# RoBeast_Power_Linear.net
KiCad netlist of a schematic drawn in Altium Designer
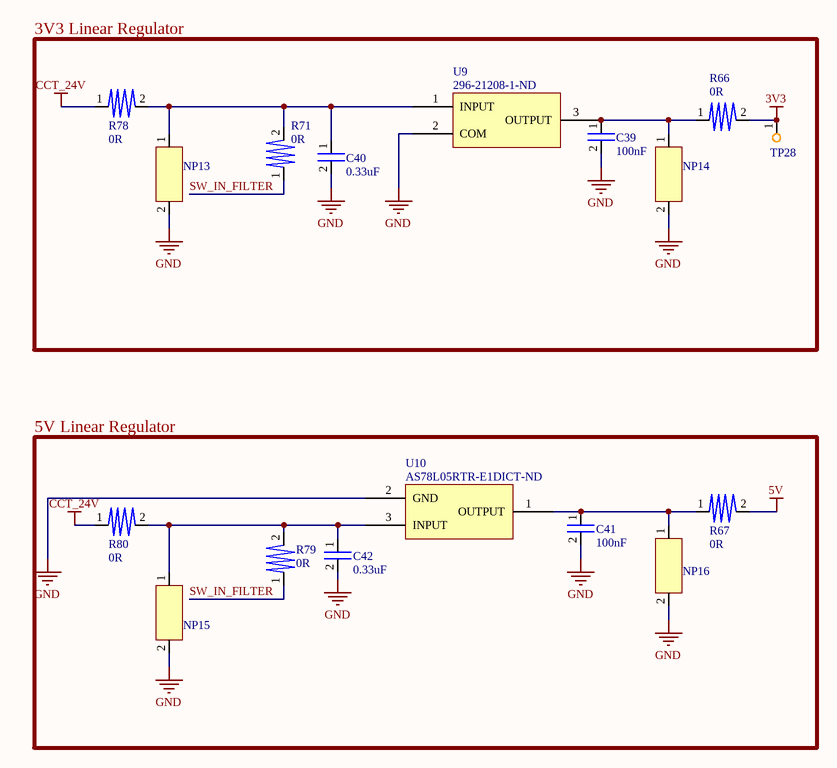
[diagram p0: RoBeast_Power_Linear.SchDoc]

(export (version "E")
  (design (tool "Eeschema 10.0.6"))
  (components
    (comp (ref "C39")
      (value "100nF")
      (footprint "0805")
      (fields
        (field (name "MANUFACTURER") "KEMET")
        (field (name "MANUFACTURER PART NUMBER") "C0805C104J5RACTU")
      )
      (libsource (lib "RoBeast_Schematic_Library") (part "C0805C104J5RAC7800"))
    )
    (comp (ref "C40")
      (value "0.33uF")
      (footprint "0805")
      (fields
        (field (name "MANUFACTURER") "KEMET")
        (field (name "MANUFACTURER PART NUMBER") "C0805C334K5RACTU")
      )
      (libsource (lib "RoBeast_Schematic_Library") (part "C0805C334K5RAC7800"))
    )
    (comp (ref "C41")
      (value "100nF")
      (footprint "0805")
      (fields
        (field (name "MANUFACTURER") "KEMET")
        (field (name "MANUFACTURER PART NUMBER") "C0805C104J5RACTU")
      )
      (libsource (lib "RoBeast_Schematic_Library") (part "C0805C104J5RAC7800"))
    )
    (comp (ref "C42")
      (value "0.33uF")
      (footprint "0805")
      (fields
        (field (name "MANUFACTURER") "KEMET")
        (field (name "MANUFACTURER PART NUMBER") "C0805C334K5RACTU")
      )
      (libsource (lib "RoBeast_Schematic_Library") (part "C0805C334K5RAC7800"))
    )
    (comp (ref "NP13")
      (value "Not Populated")
      (footprint "0805")
      (libsource (lib "RoBeast_Schematic_Library") (part "NP"))
    )
    (comp (ref "NP14")
      (value "Not Populated")
      (footprint "0805")
      (libsource (lib "RoBeast_Schematic_Library") (part "NP"))
    )
    (comp (ref "NP15")
      (value "Not Populated")
      (footprint "0805")
      (libsource (lib "RoBeast_Schematic_Library") (part "NP"))
    )
    (comp (ref "NP16")
      (value "Not Populated")
      (footprint "0805")
      (libsource (lib "RoBeast_Schematic_Library") (part "NP"))
    )
    (comp (ref "R66")
      (value "0R")
      (footprint "0805")
      (description "Fixed Resistor, Metal Glaze/thick Film, 0.125W, 0ohm, Surface Mount, 0805")
      (fields
        (field (name "MANUFACTURER") "Stackpole Electronics")
        (field (name "MANUFACTURER PART NUMBER") "RMCF0805ZT0R00")
      )
      (libsource (lib "RoBeast_Schematic_Library") (part "RMCF0805ZT0R00"))
    )
    (comp (ref "R67")
      (value "0R")
      (footprint "0805")
      (description "Fixed Resistor, Metal Glaze/thick Film, 0.125W, 0ohm, Surface Mount, 0805")
      (fields
        (field (name "MANUFACTURER") "Stackpole Electronics")
        (field (name "MANUFACTURER PART NUMBER") "RMCF0805ZT0R00")
      )
      (libsource (lib "RoBeast_Schematic_Library") (part "RMCF0805ZT0R00"))
    )
    (comp (ref "R71")
      (value "0R")
      (footprint "0805")
      (description "Fixed Resistor, Metal Glaze/thick Film, 0.125W, 0ohm, Surface Mount, 0805")
      (fields
        (field (name "MANUFACTURER") "Stackpole Electronics")
        (field (name "MANUFACTURER PART NUMBER") "RMCF0805ZT0R00")
      )
      (libsource (lib "RoBeast_Schematic_Library") (part "RMCF0805ZT0R00"))
    )
    (comp (ref "R78")
      (value "0R")
      (footprint "0805")
      (description "Fixed Resistor, Metal Glaze/thick Film, 0.125W, 0ohm, Surface Mount, 0805")
      (fields
        (field (name "MANUFACTURER") "Stackpole Electronics")
        (field (name "MANUFACTURER PART NUMBER") "RMCF0805ZT0R00")
      )
      (libsource (lib "RoBeast_Schematic_Library") (part "RMCF0805ZT0R00"))
    )
    (comp (ref "R79")
      (value "0R")
      (footprint "0805")
      (description "Fixed Resistor, Metal Glaze/thick Film, 0.125W, 0ohm, Surface Mount, 0805")
      (fields
        (field (name "MANUFACTURER") "Stackpole Electronics")
        (field (name "MANUFACTURER PART NUMBER") "RMCF0805ZT0R00")
      )
      (libsource (lib "RoBeast_Schematic_Library") (part "RMCF0805ZT0R00"))
    )
    (comp (ref "R80")
      (value "0R")
      (footprint "0805")
      (description "Fixed Resistor, Metal Glaze/thick Film, 0.125W, 0ohm, Surface Mount, 0805")
      (fields
        (field (name "MANUFACTURER") "Stackpole Electronics")
        (field (name "MANUFACTURER PART NUMBER") "RMCF0805ZT0R00")
      )
      (libsource (lib "RoBeast_Schematic_Library") (part "RMCF0805ZT0R00"))
    )
    (comp (ref "TP28")
      (value "Test Point")
      (footprint "Test Point")
      (libsource (lib "RoBeast_Schematic_Library") (part "Test Point"))
    )
    (comp (ref "U9")
      (value "Fixed 3V3 Voltage Regulator")
      (footprint "UA78M33CKVURG3")
      (description "Fixed Positive Standard Regulator, 3.3VBIPolar, PSSO2")
      (fields
        (field (name "MANUFACTURER") "Texas Instruments")
        (field (name "MANUFACTURER PART NUMBER") "UA78M33CKVURG3")
        (field (name "SUPPLIER PART NUMBER 1") "296-21208-1-ND")
      )
      (libsource (lib "RoBeast_Schematic_Library") (part "UA78M33CKVURG3"))
    )
    (comp (ref "U10")
      (value "Fixed 5V Linear Regulator")
      (footprint "AS78L05RTR-E1")
      (description "Fixed Positive Standard Regulator, 5VBIPolar")
      (fields
        (field (name "MANUFACTURER") "Diodes")
        (field (name "MANUFACTURER PART NUMBER") "AS78L05RTR-E1")
        (field (name "SUPPLIER PART NUMBER 1") "AS78L05RTR-E1DICT-ND")
      )
      (libsource (lib "RoBeast_Schematic_Library") (part "AS78L05RTR-E1"))
    )
  )
  (nets
    (net (code "1") (name "/SW_IN_FILTER") (class "Default")
      (node (ref "R71") (pin "1") (pinfunction "1_1") (pintype "passive"))
      (node (ref "R79") (pin "1") (pinfunction "1_1") (pintype "passive"))
    )
    (net (code "2") (name "3V3") (class "Default")
      (node (ref "R66") (pin "2") (pinfunction "2_2") (pintype "passive"))
      (node (ref "TP28") (pin "1") (pinfunction "1_1") (pintype "passive"))
    )
    (net (code "3") (name "5V") (class "Default")
      (node (ref "R67") (pin "2") (pinfunction "2_2") (pintype "passive"))
    )
    (net (code "4") (name "CCT_24V") (class "Default")
      (node (ref "R78") (pin "1") (pinfunction "1_1") (pintype "passive"))
      (node (ref "R80") (pin "1") (pinfunction "1_1") (pintype "passive"))
    )
    (net (code "5") (name "GND") (class "Default")
      (node (ref "C39") (pin "2") (pinfunction "2_2") (pintype "passive"))
      (node (ref "C40") (pin "2") (pinfunction "2_2") (pintype "passive"))
      (node (ref "C41") (pin "2") (pinfunction "2_2") (pintype "passive"))
      (node (ref "C42") (pin "2") (pinfunction "2_2") (pintype "passive"))
      (node (ref "NP13") (pin "2") (pinfunction "2_2") (pintype "passive"))
      (node (ref "NP14") (pin "2") (pinfunction "2_2") (pintype "passive"))
      (node (ref "NP15") (pin "2") (pinfunction "2_2") (pintype "passive"))
      (node (ref "NP16") (pin "2") (pinfunction "2_2") (pintype "passive"))
      (node (ref "U10") (pin "2") (pinfunction "GND_2") (pintype "passive"))
      (node (ref "U9") (pin "2") (pinfunction "COM_2") (pintype "passive"))
    )
    (net (code "6") (name "Net-(U9-INPUT)") (class "Default")
      (node (ref "C40") (pin "1") (pinfunction "1_1") (pintype "passive"))
      (node (ref "NP13") (pin "1") (pinfunction "1_1") (pintype "passive"))
      (node (ref "R71") (pin "2") (pinfunction "2_2") (pintype "passive"))
      (node (ref "R78") (pin "2") (pinfunction "2_2") (pintype "passive"))
      (node (ref "U9") (pin "1") (pinfunction "INPUT_1") (pintype "passive"))
    )
    (net (code "7") (name "Net-(U9-OUTPUT)") (class "Default")
      (node (ref "C39") (pin "1") (pinfunction "1_1") (pintype "passive"))
      (node (ref "NP14") (pin "1") (pinfunction "1_1") (pintype "passive"))
      (node (ref "R66") (pin "1") (pinfunction "1_1") (pintype "passive"))
      (node (ref "U9") (pin "3") (pinfunction "OUTPUT_3") (pintype "passive"))
    )
    (net (code "8") (name "Net-(U10-INPUT)") (class "Default")
      (node (ref "C42") (pin "1") (pinfunction "1_1") (pintype "passive"))
      (node (ref "NP15") (pin "1") (pinfunction "1_1") (pintype "passive"))
      (node (ref "R79") (pin "2") (pinfunction "2_2") (pintype "passive"))
      (node (ref "R80") (pin "2") (pinfunction "2_2") (pintype "passive"))
      (node (ref "U10") (pin "3") (pinfunction "INPUT_3") (pintype "passive"))
    )
    (net (code "9") (name "Net-(U10-OUTPUT)") (class "Default")
      (node (ref "C41") (pin "1") (pinfunction "1_1") (pintype "passive"))
      (node (ref "NP16") (pin "1") (pinfunction "1_1") (pintype "passive"))
      (node (ref "R67") (pin "1") (pinfunction "1_1") (pintype "passive"))
      (node (ref "U10") (pin "1") (pinfunction "OUTPUT_1") (pintype "passive"))
    )
  )
)
